# tiny.net
KiCad netlist of a schematic drawn in EAGLE
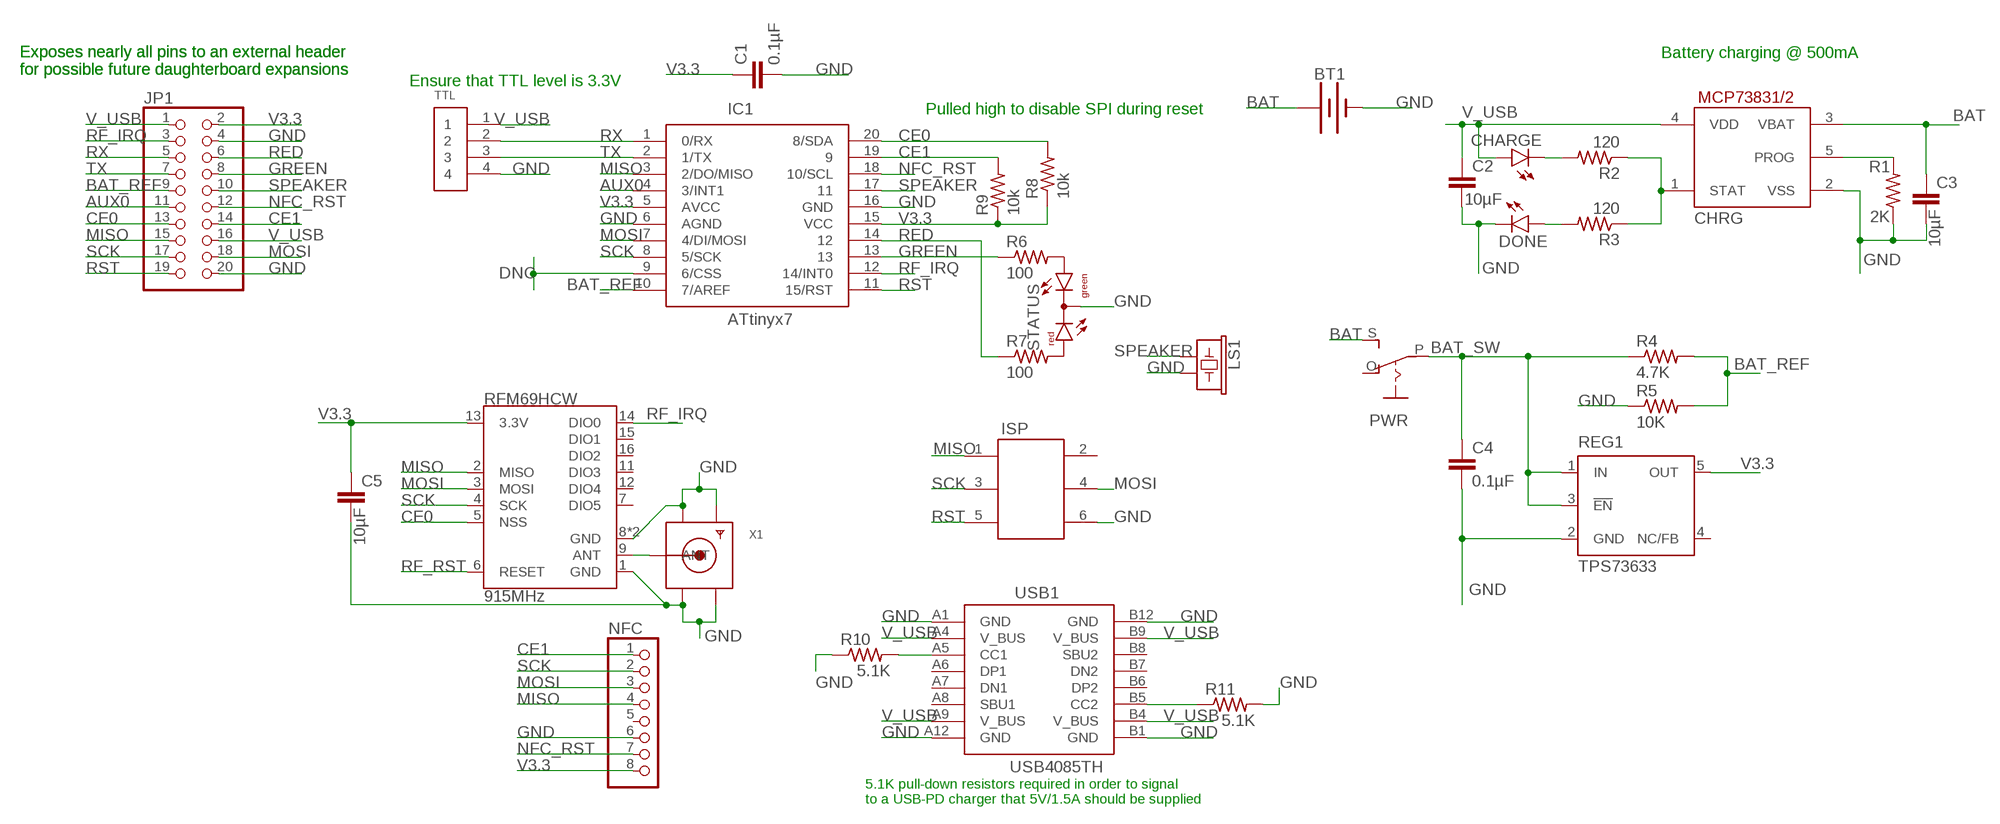
[diagram p0: schematic, sheet 1]

(export (version "E")
  (design (tool "Eeschema 10.0.6"))
  (components
    (comp (ref "BT1")
      (value "BATTERY-18650")
      (footprint "eagle-import:BATTERY_18650-HOLDER")
      (libsource (lib "eagle-import") (part "BATTERY-18650"))
    )
    (comp (ref "C1")
      (value "0.1µF")
      (footprint "eagle-import:C025-025X050")
      (libsource (lib "eagle-import") (part "C-EU025-025X050"))
    )
    (comp (ref "C2")
      (value "10µF")
      (footprint "eagle-import:C050-030X075")
      (libsource (lib "eagle-import") (part "C-EU050-030X075"))
    )
    (comp (ref "C3")
      (value "10µF")
      (footprint "eagle-import:C050-030X075")
      (libsource (lib "eagle-import") (part "C-EU050-030X075"))
    )
    (comp (ref "C4")
      (value "0.1µF")
      (footprint "eagle-import:C025-025X050")
      (libsource (lib "eagle-import") (part "C-EU025-025X050"))
    )
    (comp (ref "C5")
      (value "10µF")
      (footprint "eagle-import:C025-025X050")
      (libsource (lib "eagle-import") (part "C-EU025-025X050"))
    )
    (comp (ref "CHARGE")
      (value "LED3MM")
      (footprint "eagle-import:LED3MM")
      (libsource (lib "eagle-import") (part "LED3MM"))
    )
    (comp (ref "CHRG")
      (value "MCP73831/OT")
      (footprint "eagle-import:SOT23-5L")
      (libsource (lib "eagle-import") (part "MCP73831/OT"))
    )
    (comp (ref "DONE")
      (value "LED3MM")
      (footprint "eagle-import:LED3MM")
      (libsource (lib "eagle-import") (part "LED3MM"))
    )
    (comp (ref "IC1")
      (value "ATtinyx7")
      (footprint "eagle-import:SOIC127P1030X265-20N")
      (libsource (lib "eagle-import") (part "ATTINY167"))
    )
    (comp (ref "ISP")
      (value "61200621621")
      (footprint "eagle-import:61200621621")
      (libsource (lib "eagle-import") (part "61200621621"))
    )
    (comp (ref "JP1")
      (value "PINHD-2X10")
      (footprint "eagle-import:2X10")
      (libsource (lib "eagle-import") (part "PINHD-2X10"))
    )
    (comp (ref "LS1")
      (value "Buzz Buzz")
      (footprint "eagle-import:BUZZER-12MM")
      (libsource (lib "eagle-import") (part "BUZZER-PTH"))
    )
    (comp (ref "NFC")
      (value "PINHD-1X8BIG")
      (footprint "eagle-import:1X08-BIG")
      (libsource (lib "eagle-import") (part "PINHD-1X8BIG"))
    )
    (comp (ref "PWR")
      (value "EG1218S")
      (footprint "eagle-import:EG1218")
      (libsource (lib "eagle-import") (part "EG1218S"))
    )
    (comp (ref "R1")
      (value "2K")
      (footprint "eagle-import:0204_5")
      (libsource (lib "eagle-import") (part "R-US_0204/5"))
    )
    (comp (ref "R2")
      (value "120")
      (footprint "eagle-import:0204_5")
      (libsource (lib "eagle-import") (part "R-US_0204/5"))
    )
    (comp (ref "R3")
      (value "120")
      (footprint "eagle-import:0204_5")
      (libsource (lib "eagle-import") (part "R-US_0204/5"))
    )
    (comp (ref "R4")
      (value "4.7K")
      (footprint "eagle-import:0204_5")
      (libsource (lib "eagle-import") (part "R-US_0204/5"))
    )
    (comp (ref "R5")
      (value "10K")
      (footprint "eagle-import:0204_5")
      (libsource (lib "eagle-import") (part "R-US_0204/5"))
    )
    (comp (ref "R6")
      (value "100")
      (footprint "eagle-import:0204_5")
      (libsource (lib "eagle-import") (part "R-US_0204/5"))
    )
    (comp (ref "R7")
      (value "100")
      (footprint "eagle-import:0204_5")
      (libsource (lib "eagle-import") (part "R-US_0204/5"))
    )
    (comp (ref "R8")
      (value "10k")
      (footprint "eagle-import:0204_5")
      (libsource (lib "eagle-import") (part "R-US_0204/5"))
    )
    (comp (ref "R9")
      (value "10k")
      (footprint "eagle-import:0204_5")
      (libsource (lib "eagle-import") (part "R-US_0204/5"))
    )
    (comp (ref "R10")
      (value "5.1K")
      (footprint "eagle-import:0204_5")
      (libsource (lib "eagle-import") (part "R-US_0204/5"))
    )
    (comp (ref "R11")
      (value "5.1K")
      (footprint "eagle-import:0204_5")
      (libsource (lib "eagle-import") (part "R-US_0204/5"))
    )
    (comp (ref "REG1")
      (value "TPS73633")
      (footprint "eagle-import:SOT23-DBV")
      (fields (field (name "MF") "TEXAS INSTRUMENTS") (field (name "MPN") "TPS77001DBVT"))
      (libsource (lib "eagle-import") (part "TPS77001"))
    )
    (comp (ref "RFM69HCW")
      (value "915MHz")
      (footprint "eagle-import:RFM69HCW-XXXS2")
      (libsource (lib "eagle-import") (part "RFM69HCW-433"))
    )
    (comp (ref "STATUS")
      (value "DUOLED-RG-C")
      (footprint "eagle-import:DUOLED-C-5MM")
      (libsource (lib "eagle-import") (part "DUOLED-RG-C"))
    )
    (comp (ref "TTL")
      (value "1X4-BIG")
      (footprint "eagle-import:1X04-BIG")
      (libsource (lib "eagle-import") (part "1X4-BIG"))
    )
    (comp (ref "USB1")
      (value "USB4085TH")
      (footprint "eagle-import:USB4085")
      (libsource (lib "eagle-import") (part "USB4085TH"))
    )
    (comp (ref "X1")
      (value "SMACONNECTOR_EDGE")
      (footprint "eagle-import:SMA_EDGELAUNCH")
      (libsource (lib "eagle-import") (part "SMACONNECTOR_EDGE"))
    )
  )
  (nets
    (net (code "1") (name "/AUX0") (class "Default")
      (node (ref "IC1") (pin "4") (pinfunction "3/INT1_4") (pintype "bidirectional"))
      (node (ref "JP1") (pin "11") (pinfunction "11_11") (pintype "passive"))
    )
    (net (code "2") (name "/BAT") (class "Default")
      (node (ref "BT1") (pin "PWR@1") (pinfunction "+_PWR@1") (pintype "power_in"))
      (node (ref "BT1") (pin "PWR@2") (pinfunction "+_PWR@2") (pintype "power_in"))
      (node (ref "BT1") (pin "PWR@3") (pinfunction "+_PWR@3") (pintype "power_in"))
      (node (ref "C3") (pin "1") (pinfunction "1_1") (pintype "passive"))
      (node (ref "CHRG") (pin "3") (pinfunction "VBAT_3") (pintype "bidirectional"))
      (node (ref "PWR") (pin "S") (pinfunction "S_S") (pintype "passive"))
    )
    (net (code "3") (name "/BAT_REF") (class "Default")
      (node (ref "IC1") (pin "10") (pinfunction "7/AREF_10") (pintype "bidirectional"))
      (node (ref "JP1") (pin "9") (pinfunction "9_9") (pintype "passive"))
      (node (ref "R4") (pin "2") (pinfunction "2_2") (pintype "passive"))
      (node (ref "R5") (pin "2") (pinfunction "2_2") (pintype "passive"))
    )
    (net (code "4") (name "/BAT_SW") (class "Default")
      (node (ref "C4") (pin "1") (pinfunction "1_1") (pintype "passive"))
      (node (ref "PWR") (pin "P") (pinfunction "P_P") (pintype "passive"))
      (node (ref "R4") (pin "1") (pinfunction "1_1") (pintype "passive"))
      (node (ref "REG1") (pin "1") (pinfunction "IN_1") (pintype "input"))
      (node (ref "REG1") (pin "3") (pinfunction "~{EN}_3") (pintype "input"))
    )
    (net (code "5") (name "/CE0") (class "Default")
      (node (ref "IC1") (pin "20") (pinfunction "8/SDA_20") (pintype "bidirectional"))
      (node (ref "JP1") (pin "13") (pinfunction "13_13") (pintype "passive"))
      (node (ref "R8") (pin "2") (pinfunction "2_2") (pintype "passive"))
      (node (ref "RFM69HCW") (pin "5") (pinfunction "NSS_5") (pintype "input"))
    )
    (net (code "6") (name "/CE1") (class "Default")
      (node (ref "IC1") (pin "19") (pinfunction "9_19") (pintype "bidirectional"))
      (node (ref "JP1") (pin "14") (pinfunction "14_14") (pintype "passive"))
      (node (ref "NFC") (pin "1") (pinfunction "1_1") (pintype "passive"))
      (node (ref "R9") (pin "2") (pinfunction "2_2") (pintype "passive"))
    )
    (net (code "7") (name "/DNC") (class "Default")
      (node (ref "IC1") (pin "9") (pinfunction "6/CSS_9") (pintype "bidirectional"))
    )
    (net (code "8") (name "/GND") (class "Default")
      (node (ref "BT1") (pin "GND@1") (pinfunction "-_GND@1") (pintype "power_in"))
      (node (ref "BT1") (pin "GND@2") (pinfunction "-_GND@2") (pintype "power_in"))
      (node (ref "BT1") (pin "GND@3") (pinfunction "-_GND@3") (pintype "power_in"))
      (node (ref "C1") (pin "2") (pinfunction "2_2") (pintype "passive"))
      (node (ref "C2") (pin "2") (pinfunction "2_2") (pintype "passive"))
      (node (ref "C3") (pin "2") (pinfunction "2_2") (pintype "passive"))
      (node (ref "C4") (pin "2") (pinfunction "2_2") (pintype "passive"))
      (node (ref "C5") (pin "2") (pinfunction "2_2") (pintype "passive"))
      (node (ref "CHRG") (pin "2") (pinfunction "VSS_2") (pintype "power_in"))
      (node (ref "DONE") (pin "K") (pinfunction "C_K") (pintype "passive"))
      (node (ref "IC1") (pin "16") (pinfunction "GND_16") (pintype "power_in"))
      (node (ref "IC1") (pin "6") (pinfunction "AGND_6") (pintype "power_in"))
      (node (ref "ISP") (pin "6") (pinfunction "6_6") (pintype "passive"))
      (node (ref "JP1") (pin "20") (pinfunction "20_20") (pintype "passive"))
      (node (ref "JP1") (pin "4") (pinfunction "4_4") (pintype "passive"))
      (node (ref "LS1") (pin "-") (pinfunction "2_-") (pintype "passive"))
      (node (ref "NFC") (pin "6") (pinfunction "6_6") (pintype "passive"))
      (node (ref "R1") (pin "1") (pinfunction "1_1") (pintype "passive"))
      (node (ref "R10") (pin "1") (pinfunction "1_1") (pintype "passive"))
      (node (ref "R11") (pin "2") (pinfunction "2_2") (pintype "passive"))
      (node (ref "R5") (pin "1") (pinfunction "1_1") (pintype "passive"))
      (node (ref "REG1") (pin "2") (pinfunction "GND_2") (pintype "power_in"))
      (node (ref "RFM69HCW") (pin "1") (pinfunction "GND_1") (pintype "power_in"))
      (node (ref "RFM69HCW") (pin "10") (pinfunction "GND_10") (pintype "power_in"))
      (node (ref "RFM69HCW") (pin "8") (pinfunction "GND_8") (pintype "power_in"))
      (node (ref "STATUS") (pin "C") (pinfunction "C_C") (pintype "passive"))
      (node (ref "TTL") (pin "4") (pinfunction "4_4") (pintype "bidirectional"))
      (node (ref "USB1") (pin "A1") (pinfunction "GND_A1") (pintype "power_in"))
      (node (ref "USB1") (pin "A12") (pinfunction "GND_A12") (pintype "power_in"))
      (node (ref "USB1") (pin "B1") (pinfunction "GND_B1") (pintype "power_in"))
      (node (ref "USB1") (pin "B12") (pinfunction "GND_B12") (pintype "power_in"))
      (node (ref "X1") (pin "GND@1") (pinfunction "GND4_GND@1") (pintype "power_in"))
      (node (ref "X1") (pin "GND@2") (pinfunction "GND3_GND@2") (pintype "power_in"))
      (node (ref "X1") (pin "GND@3") (pinfunction "GND2_GND@3") (pintype "power_in"))
      (node (ref "X1") (pin "GND@4") (pinfunction "GND1_GND@4") (pintype "power_in"))
    )
    (net (code "9") (name "/GREEN") (class "Default")
      (node (ref "IC1") (pin "13") (pinfunction "13_13") (pintype "bidirectional"))
      (node (ref "JP1") (pin "8") (pinfunction "8_8") (pintype "passive"))
      (node (ref "R6") (pin "1") (pinfunction "1_1") (pintype "passive"))
    )
    (net (code "10") (name "/MISO") (class "Default")
      (node (ref "IC1") (pin "3") (pinfunction "2/DO/MISO_3") (pintype "bidirectional"))
      (node (ref "ISP") (pin "1") (pinfunction "1_1") (pintype "passive"))
      (node (ref "JP1") (pin "15") (pinfunction "15_15") (pintype "passive"))
      (node (ref "NFC") (pin "4") (pinfunction "4_4") (pintype "passive"))
      (node (ref "RFM69HCW") (pin "2") (pinfunction "MISO_2") (pintype "bidirectional"))
    )
    (net (code "11") (name "/MOSI") (class "Default")
      (node (ref "IC1") (pin "7") (pinfunction "4/DI/MOSI_7") (pintype "bidirectional"))
      (node (ref "ISP") (pin "4") (pinfunction "4_4") (pintype "passive"))
      (node (ref "JP1") (pin "18") (pinfunction "18_18") (pintype "passive"))
      (node (ref "NFC") (pin "3") (pinfunction "3_3") (pintype "passive"))
      (node (ref "RFM69HCW") (pin "3") (pinfunction "MOSI_3") (pintype "input"))
    )
    (net (code "12") (name "/NFC_RST") (class "Default")
      (node (ref "IC1") (pin "18") (pinfunction "10/SCL_18") (pintype "bidirectional"))
      (node (ref "JP1") (pin "12") (pinfunction "12_12") (pintype "passive"))
      (node (ref "NFC") (pin "7") (pinfunction "7_7") (pintype "passive"))
    )
    (net (code "13") (name "/RED") (class "Default")
      (node (ref "IC1") (pin "14") (pinfunction "12_14") (pintype "bidirectional"))
      (node (ref "JP1") (pin "6") (pinfunction "6_6") (pintype "passive"))
      (node (ref "R7") (pin "1") (pinfunction "1_1") (pintype "passive"))
    )
    (net (code "14") (name "/RF_IRQ") (class "Default")
      (node (ref "IC1") (pin "12") (pinfunction "14/INT0_12") (pintype "bidirectional"))
      (node (ref "JP1") (pin "3") (pinfunction "3_3") (pintype "passive"))
      (node (ref "RFM69HCW") (pin "14") (pinfunction "DIO0_14") (pintype "bidirectional"))
    )
    (net (code "15") (name "/RF_RST") (class "Default")
      (node (ref "RFM69HCW") (pin "6") (pinfunction "RESET_6") (pintype "input"))
    )
    (net (code "16") (name "/RST") (class "Default")
      (node (ref "IC1") (pin "11") (pinfunction "15/RST_11") (pintype "bidirectional"))
      (node (ref "ISP") (pin "5") (pinfunction "5_5") (pintype "passive"))
      (node (ref "JP1") (pin "19") (pinfunction "19_19") (pintype "passive"))
    )
    (net (code "17") (name "/RX") (class "Default")
      (node (ref "IC1") (pin "1") (pinfunction "0/RX_1") (pintype "bidirectional"))
      (node (ref "JP1") (pin "5") (pinfunction "5_5") (pintype "passive"))
      (node (ref "TTL") (pin "2") (pinfunction "2_2") (pintype "bidirectional"))
    )
    (net (code "18") (name "/SCK") (class "Default")
      (node (ref "IC1") (pin "8") (pinfunction "5/SCK_8") (pintype "bidirectional"))
      (node (ref "ISP") (pin "3") (pinfunction "3_3") (pintype "passive"))
      (node (ref "JP1") (pin "17") (pinfunction "17_17") (pintype "passive"))
      (node (ref "NFC") (pin "2") (pinfunction "2_2") (pintype "passive"))
      (node (ref "RFM69HCW") (pin "4") (pinfunction "SCK_4") (pintype "input"))
    )
    (net (code "19") (name "/SPEAKER") (class "Default")
      (node (ref "IC1") (pin "17") (pinfunction "11_17") (pintype "bidirectional"))
      (node (ref "JP1") (pin "10") (pinfunction "10_10") (pintype "passive"))
      (node (ref "LS1") (pin "+") (pinfunction "1_+") (pintype "passive"))
    )
    (net (code "20") (name "/TX") (class "Default")
      (node (ref "IC1") (pin "2") (pinfunction "1/TX_2") (pintype "bidirectional"))
      (node (ref "JP1") (pin "7") (pinfunction "7_7") (pintype "passive"))
      (node (ref "TTL") (pin "3") (pinfunction "3_3") (pintype "bidirectional"))
    )
    (net (code "21") (name "/V3.3") (class "Default")
      (node (ref "C1") (pin "1") (pinfunction "1_1") (pintype "passive"))
      (node (ref "C5") (pin "1") (pinfunction "1_1") (pintype "passive"))
      (node (ref "IC1") (pin "15") (pinfunction "VCC_15") (pintype "power_in"))
      (node (ref "IC1") (pin "5") (pinfunction "AVCC_5") (pintype "power_in"))
      (node (ref "JP1") (pin "2") (pinfunction "2_2") (pintype "passive"))
      (node (ref "NFC") (pin "8") (pinfunction "8_8") (pintype "passive"))
      (node (ref "R8") (pin "1") (pinfunction "1_1") (pintype "passive"))
      (node (ref "R9") (pin "1") (pinfunction "1_1") (pintype "passive"))
      (node (ref "REG1") (pin "5") (pinfunction "OUT_5") (pintype "passive"))
      (node (ref "RFM69HCW") (pin "13") (pinfunction "3.3V_13") (pintype "power_in"))
    )
    (net (code "22") (name "/V_USB") (class "Default")
      (node (ref "C2") (pin "1") (pinfunction "1_1") (pintype "passive"))
      (node (ref "CHARGE") (pin "A") (pinfunction "A_A") (pintype "passive"))
      (node (ref "CHRG") (pin "4") (pinfunction "VDD_4") (pintype "power_in"))
      (node (ref "JP1") (pin "1") (pinfunction "1_1") (pintype "passive"))
      (node (ref "JP1") (pin "16") (pinfunction "16_16") (pintype "passive"))
      (node (ref "TTL") (pin "1") (pinfunction "1_1") (pintype "bidirectional"))
      (node (ref "USB1") (pin "A4") (pinfunction "V_BUS_A4") (pintype "power_in"))
      (node (ref "USB1") (pin "A9") (pinfunction "V_BUS_A9") (pintype "power_in"))
      (node (ref "USB1") (pin "B4") (pinfunction "V_BUS_B4") (pintype "power_in"))
      (node (ref "USB1") (pin "B9") (pinfunction "V_BUS_B9") (pintype "power_in"))
    )
    (net (code "23") (name "Net-(CHARGE-C)") (class "Default")
      (node (ref "CHARGE") (pin "K") (pinfunction "C_K") (pintype "passive"))
      (node (ref "R2") (pin "2") (pinfunction "2_2") (pintype "passive"))
    )
    (net (code "24") (name "Net-(CHRG-PROG)") (class "Default")
      (node (ref "CHRG") (pin "5") (pinfunction "PROG_5") (pintype "input"))
      (node (ref "R1") (pin "2") (pinfunction "2_2") (pintype "passive"))
    )
    (net (code "25") (name "Net-(CHRG-STAT)") (class "Default")
      (node (ref "CHRG") (pin "1") (pinfunction "STAT_1") (pintype "output"))
      (node (ref "R2") (pin "1") (pinfunction "1_1") (pintype "passive"))
      (node (ref "R3") (pin "1") (pinfunction "1_1") (pintype "passive"))
    )
    (net (code "26") (name "Net-(DONE-PadA)") (class "Default")
      (node (ref "DONE") (pin "A") (pinfunction "A_A") (pintype "passive"))
      (node (ref "R3") (pin "2") (pinfunction "2_2") (pintype "passive"))
    )
    (net (code "27") (name "Net-(R7-Pad2)") (class "Default")
      (node (ref "R7") (pin "2") (pinfunction "2_2") (pintype "passive"))
      (node (ref "STATUS") (pin "AR") (pinfunction "AR_AR") (pintype "passive"))
    )
    (net (code "28") (name "Net-(RFM69HCW-ANT)") (class "Default")
      (node (ref "RFM69HCW") (pin "9") (pinfunction "ANT_9") (pintype "passive"))
      (node (ref "X1") (pin "P") (pinfunction "ANT_P") (pintype "bidirectional"))
    )
    (net (code "29") (name "Net-(STATUS-AG)") (class "Default")
      (node (ref "R6") (pin "2") (pinfunction "2_2") (pintype "passive"))
      (node (ref "STATUS") (pin "AX") (pinfunction "AG_AX") (pintype "passive"))
    )
    (net (code "30") (name "Net-(USB1-CC1)") (class "Default")
      (node (ref "R10") (pin "2") (pinfunction "2_2") (pintype "passive"))
      (node (ref "USB1") (pin "A5") (pinfunction "CC1_A5") (pintype "bidirectional"))
    )
    (net (code "31") (name "Net-(USB1-CC2)") (class "Default")
      (node (ref "R11") (pin "1") (pinfunction "1_1") (pintype "passive"))
      (node (ref "USB1") (pin "B5") (pinfunction "CC2_B5") (pintype "bidirectional"))
    )
    (net (code "32") (name "unconnected-(ISP-Pad2)") (class "Default")
      (node (ref "ISP") (pin "2") (pinfunction "2_2") (pintype "passive"))
    )
    (net (code "33") (name "unconnected-(NFC-Pad5)") (class "Default")
      (node (ref "NFC") (pin "5") (pinfunction "5_5") (pintype "passive"))
    )
    (net (code "34") (name "unconnected-(PWR-PadO)") (class "Default")
      (node (ref "PWR") (pin "O") (pinfunction "O_O") (pintype "passive"))
    )
    (net (code "35") (name "unconnected-(REG1-NC{slash}FB-Pad4)") (class "Default")
      (node (ref "REG1") (pin "4") (pinfunction "NC/FB_4") (pintype "passive"))
    )
    (net (code "36") (name "unconnected-(RFM69HCW-DIO1-Pad15)") (class "Default")
      (node (ref "RFM69HCW") (pin "15") (pinfunction "DIO1_15") (pintype "bidirectional"))
    )
    (net (code "37") (name "unconnected-(RFM69HCW-DIO2-Pad16)") (class "Default")
      (node (ref "RFM69HCW") (pin "16") (pinfunction "DIO2_16") (pintype "bidirectional"))
    )
    (net (code "38") (name "unconnected-(RFM69HCW-DIO3-Pad11)") (class "Default")
      (node (ref "RFM69HCW") (pin "11") (pinfunction "DIO3_11") (pintype "bidirectional"))
    )
    (net (code "39") (name "unconnected-(RFM69HCW-DIO4-Pad12)") (class "Default")
      (node (ref "RFM69HCW") (pin "12") (pinfunction "DIO4_12") (pintype "bidirectional"))
    )
    (net (code "40") (name "unconnected-(RFM69HCW-DIO5-Pad7)") (class "Default")
      (node (ref "RFM69HCW") (pin "7") (pinfunction "DIO5_7") (pintype "bidirectional"))
    )
    (net (code "41") (name "unconnected-(USB1-DN1-PadA7)") (class "Default")
      (node (ref "USB1") (pin "A7") (pinfunction "DN1_A7") (pintype "bidirectional"))
    )
    (net (code "42") (name "unconnected-(USB1-DN2-PadB7)") (class "Default")
      (node (ref "USB1") (pin "B7") (pinfunction "DN2_B7") (pintype "bidirectional"))
    )
    (net (code "43") (name "unconnected-(USB1-DP1-PadA6)") (class "Default")
      (node (ref "USB1") (pin "A6") (pinfunction "DP1_A6") (pintype "bidirectional"))
    )
    (net (code "44") (name "unconnected-(USB1-DP2-PadB6)") (class "Default")
      (node (ref "USB1") (pin "B6") (pinfunction "DP2_B6") (pintype "bidirectional"))
    )
    (net (code "45") (name "unconnected-(USB1-SBU1-PadA8)") (class "Default")
      (node (ref "USB1") (pin "A8") (pinfunction "SBU1_A8") (pintype "bidirectional"))
    )
    (net (code "46") (name "unconnected-(USB1-SBU2-PadB8)") (class "Default")
      (node (ref "USB1") (pin "B8") (pinfunction "SBU2_B8") (pintype "bidirectional"))
    )
  )
)
